# ddrive-esp-deadrail-1-3.net
KiCad netlist of a schematic drawn in EAGLE
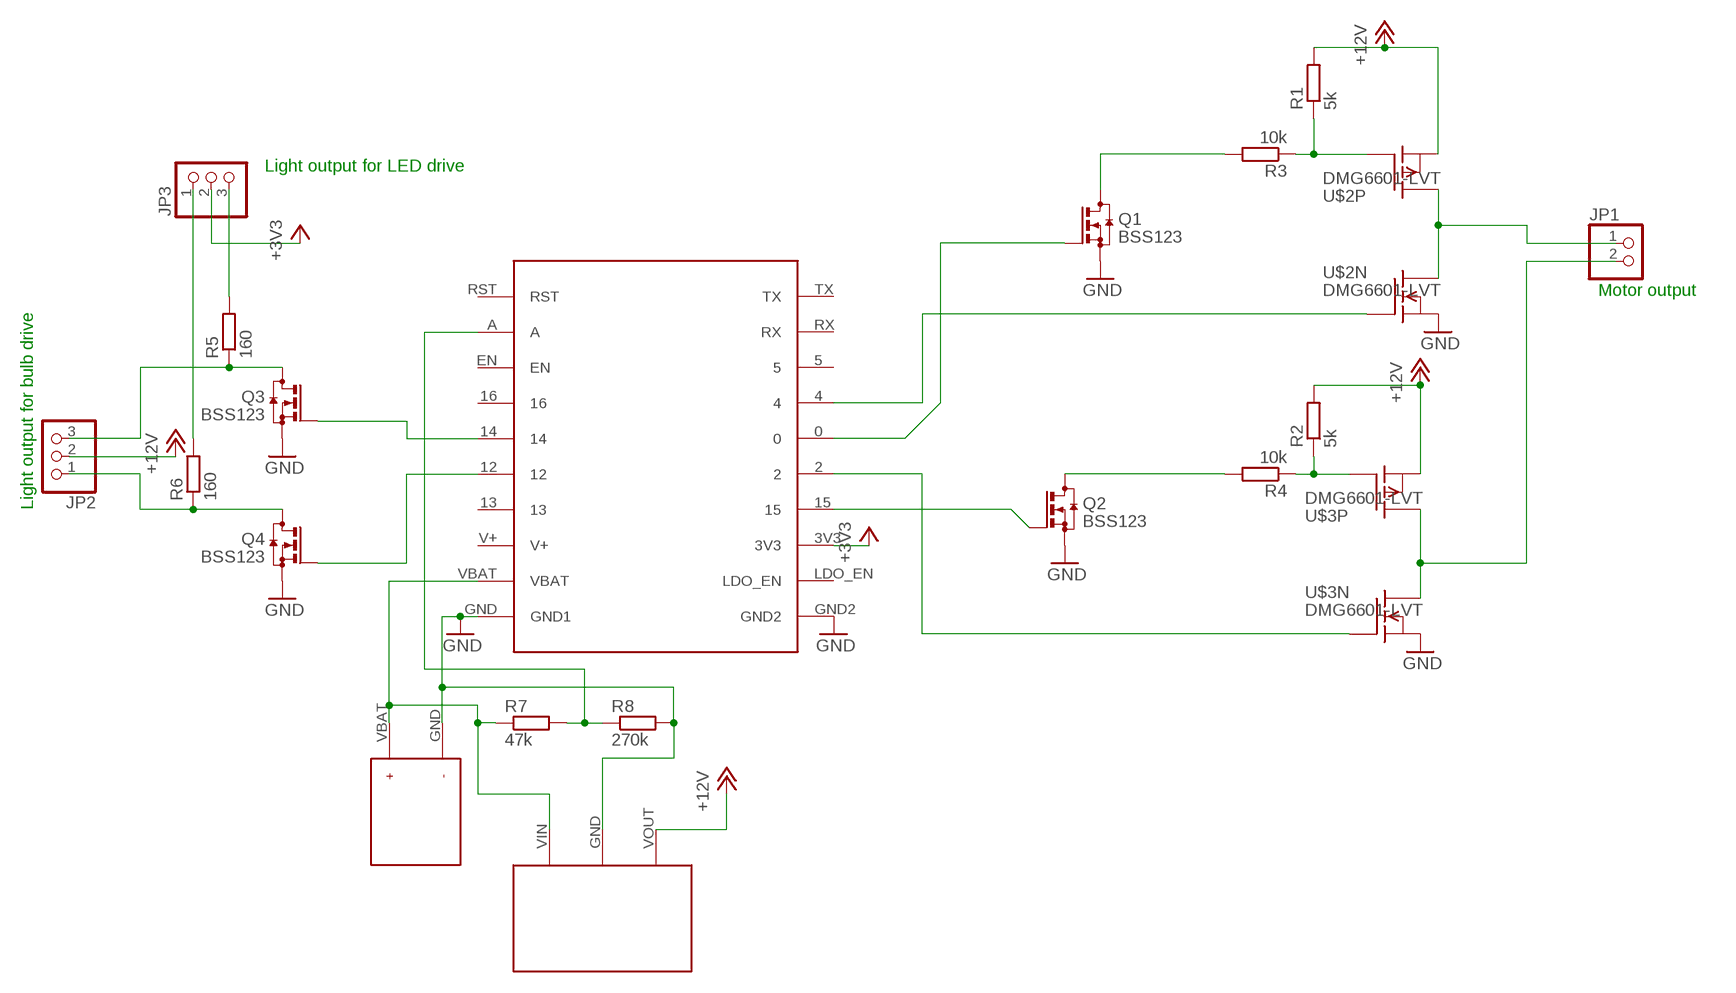
[diagram p0: schematic, sheet 1]

(export (version "E")
  (design (tool "Eeschema 10.0.6"))
  (components
    (comp (ref "JP1")
      (value "PINHD-1X2")
      (footprint "eagle-import:1X02")
      (libsource (lib "eagle-import") (part "PINHD-1X2"))
    )
    (comp (ref "JP2")
      (value "PINHD-1X3")
      (footprint "eagle-import:1X03")
      (libsource (lib "eagle-import") (part "PINHD-1X3"))
    )
    (comp (ref "JP3")
      (value "PINHD-1X3")
      (footprint "eagle-import:1X03")
      (libsource (lib "eagle-import") (part "PINHD-1X3"))
    )
    (comp (ref "Q1")
      (value "BSS123")
      (footprint "eagle-import:SOT23")
      (libsource (lib "eagle-import") (part "BSS123"))
    )
    (comp (ref "Q2")
      (value "BSS123")
      (footprint "eagle-import:SOT23")
      (libsource (lib "eagle-import") (part "BSS123"))
    )
    (comp (ref "Q3")
      (value "BSS123")
      (footprint "eagle-import:SOT23")
      (libsource (lib "eagle-import") (part "BSS123"))
    )
    (comp (ref "Q4")
      (value "BSS123")
      (footprint "eagle-import:SOT23")
      (libsource (lib "eagle-import") (part "BSS123"))
    )
    (comp (ref "R1")
      (value "5k")
      (footprint "eagle-import:R0805")
      (libsource (lib "eagle-import") (part "R-EU_R0805"))
    )
    (comp (ref "R2")
      (value "5k")
      (footprint "eagle-import:R0805")
      (libsource (lib "eagle-import") (part "R-EU_R0805"))
    )
    (comp (ref "R3")
      (value "10k")
      (footprint "eagle-import:R0805")
      (libsource (lib "eagle-import") (part "R-EU_R0805"))
    )
    (comp (ref "R4")
      (value "10k")
      (footprint "eagle-import:R0805")
      (libsource (lib "eagle-import") (part "R-EU_R0805"))
    )
    (comp (ref "R5")
      (value "160")
      (footprint "eagle-import:R0805")
      (libsource (lib "eagle-import") (part "R-EU_R0805"))
    )
    (comp (ref "R6")
      (value "160")
      (footprint "eagle-import:R0805")
      (libsource (lib "eagle-import") (part "R-EU_R0805"))
    )
    (comp (ref "R7")
      (value "47k")
      (footprint "eagle-import:R0805")
      (libsource (lib "eagle-import") (part "R-EU_R0805"))
    )
    (comp (ref "R8")
      (value "270k")
      (footprint "eagle-import:R0805")
      (libsource (lib "eagle-import") (part "R-EU_R0805"))
    )
    (comp (ref "U$1")
      (value "ESP12-HUZZAH")
      (footprint "eagle-import:ESP12-HUZZAH")
      (libsource (lib "eagle-import") (part "ESP12-HUZZAH"))
    )
    (comp (ref "U$2")
      (value "DMG6601-LVT")
      (footprint "eagle-import:TSOT-26")
      (libsource (lib "eagle-import") (part "DMG6601-LVT"))
    )
    (comp (ref "U$3")
      (value "DMG6601-LVT")
      (footprint "eagle-import:TSOT-26")
      (libsource (lib "eagle-import") (part "DMG6601-LVT"))
    )
    (comp (ref "U$4")
      (value "JST-PINHD")
      (footprint "eagle-import:JST-PINHDR")
      (libsource (lib "eagle-import") (part "JST-PINHD"))
    )
    (comp (ref "U$5")
      (value "POLOLU-VREG12")
      (footprint "eagle-import:POLOLU-REGULATOR")
      (libsource (lib "eagle-import") (part "POLOLU-VREG12"))
    )
  )
  (nets
    (net (code "1") (name "+3V3") (class "Default")
      (node (ref "JP3") (pin "2") (pinfunction "2_2") (pintype "passive"))
      (node (ref "U$1") (pin "3V3") (pinfunction "3V3_3V3") (pintype "power_in"))
    )
    (net (code "2") (name "+12V") (class "Default")
      (node (ref "JP2") (pin "2") (pinfunction "2_2") (pintype "passive"))
      (node (ref "R1") (pin "2") (pinfunction "2_2") (pintype "passive"))
      (node (ref "R2") (pin "2") (pinfunction "2_2") (pintype "passive"))
      (node (ref "U$2") (pin "2") (pinfunction "S_2") (pintype "passive"))
      (node (ref "U$3") (pin "2") (pinfunction "S_2") (pintype "passive"))
      (node (ref "U$5") (pin "VOUT") (pinfunction "VOUT_VOUT") (pintype "bidirectional"))
    )
    (net (code "3") (name "/V+") (class "Default")
      (node (ref "U$1") (pin "V+") (pinfunction "V+_V+") (pintype "power_in"))
    )
    (net (code "4") (name "GND") (class "Default")
      (node (ref "Q1") (pin "2") (pinfunction "S_2") (pintype "passive"))
      (node (ref "Q2") (pin "2") (pinfunction "S_2") (pintype "passive"))
      (node (ref "Q3") (pin "2") (pinfunction "S_2") (pintype "passive"))
      (node (ref "Q4") (pin "2") (pinfunction "S_2") (pintype "passive"))
      (node (ref "R8") (pin "2") (pinfunction "2_2") (pintype "passive"))
      (node (ref "U$1") (pin "GND") (pinfunction "GND1_GND") (pintype "power_in"))
      (node (ref "U$1") (pin "GND2") (pinfunction "GND2_GND2") (pintype "power_in"))
      (node (ref "U$2") (pin "5") (pinfunction "S_5") (pintype "passive"))
      (node (ref "U$3") (pin "5") (pinfunction "S_5") (pintype "passive"))
      (node (ref "U$4") (pin "GND") (pinfunction "P$1_GND") (pintype "power_in"))
      (node (ref "U$5") (pin "GND") (pinfunction "GND_GND") (pintype "bidirectional"))
    )
    (net (code "5") (name "Net-(JP3-Pad1)") (class "Default")
      (node (ref "JP3") (pin "1") (pinfunction "1_1") (pintype "passive"))
      (node (ref "R6") (pin "2") (pinfunction "2_2") (pintype "passive"))
    )
    (net (code "6") (name "Net-(JP3-Pad3)") (class "Default")
      (node (ref "JP3") (pin "3") (pinfunction "3_3") (pintype "passive"))
      (node (ref "R5") (pin "2") (pinfunction "2_2") (pintype "passive"))
    )
    (net (code "7") (name "Net-(Q1-D)") (class "Default")
      (node (ref "Q1") (pin "3") (pinfunction "D_3") (pintype "passive"))
      (node (ref "R3") (pin "2") (pinfunction "2_2") (pintype "passive"))
    )
    (net (code "8") (name "Net-(Q1-G)") (class "Default")
      (node (ref "Q1") (pin "1") (pinfunction "G_1") (pintype "passive"))
      (node (ref "U$1") (pin "0") (pinfunction "0_0") (pintype "bidirectional"))
    )
    (net (code "9") (name "Net-(Q2-D)") (class "Default")
      (node (ref "Q2") (pin "3") (pinfunction "D_3") (pintype "passive"))
      (node (ref "R4") (pin "2") (pinfunction "2_2") (pintype "passive"))
    )
    (net (code "10") (name "Net-(Q2-G)") (class "Default")
      (node (ref "Q2") (pin "1") (pinfunction "G_1") (pintype "passive"))
      (node (ref "U$1") (pin "15") (pinfunction "15_15") (pintype "bidirectional"))
    )
    (net (code "11") (name "Net-(Q3-D)") (class "Default")
      (node (ref "JP2") (pin "3") (pinfunction "3_3") (pintype "passive"))
      (node (ref "Q3") (pin "3") (pinfunction "D_3") (pintype "passive"))
      (node (ref "R5") (pin "1") (pinfunction "1_1") (pintype "passive"))
    )
    (net (code "12") (name "Net-(Q3-G)") (class "Default")
      (node (ref "Q3") (pin "1") (pinfunction "G_1") (pintype "passive"))
      (node (ref "U$1") (pin "14") (pinfunction "14_14") (pintype "bidirectional"))
    )
    (net (code "13") (name "Net-(Q4-D)") (class "Default")
      (node (ref "JP2") (pin "1") (pinfunction "1_1") (pintype "passive"))
      (node (ref "Q4") (pin "3") (pinfunction "D_3") (pintype "passive"))
      (node (ref "R6") (pin "1") (pinfunction "1_1") (pintype "passive"))
    )
    (net (code "14") (name "Net-(Q4-G)") (class "Default")
      (node (ref "Q4") (pin "1") (pinfunction "G_1") (pintype "passive"))
      (node (ref "U$1") (pin "12") (pinfunction "12_12") (pintype "bidirectional"))
    )
    (net (code "15") (name "Net-(R7-Pad2)") (class "Default")
      (node (ref "R7") (pin "2") (pinfunction "2_2") (pintype "passive"))
      (node (ref "R8") (pin "1") (pinfunction "1_1") (pintype "passive"))
      (node (ref "U$1") (pin "A") (pinfunction "A_A") (pintype "bidirectional"))
    )
    (net (code "16") (name "Net-(U$2A-D)") (class "Default")
      (node (ref "JP1") (pin "1") (pinfunction "1_1") (pintype "passive"))
      (node (ref "U$2") (pin "4") (pinfunction "D_4") (pintype "passive"))
      (node (ref "U$2") (pin "6") (pinfunction "D_6") (pintype "passive"))
    )
    (net (code "17") (name "Net-(U$2A-G)") (class "Default")
      (node (ref "U$1") (pin "4") (pinfunction "4_4") (pintype "bidirectional"))
      (node (ref "U$2") (pin "1") (pinfunction "G_1") (pintype "passive"))
    )
    (net (code "18") (name "Net-(U$2B-G)") (class "Default")
      (node (ref "R1") (pin "1") (pinfunction "1_1") (pintype "passive"))
      (node (ref "R3") (pin "1") (pinfunction "1_1") (pintype "passive"))
      (node (ref "U$2") (pin "3") (pinfunction "G_3") (pintype "passive"))
    )
    (net (code "19") (name "Net-(U$3A-D)") (class "Default")
      (node (ref "JP1") (pin "2") (pinfunction "2_2") (pintype "passive"))
      (node (ref "U$3") (pin "4") (pinfunction "D_4") (pintype "passive"))
      (node (ref "U$3") (pin "6") (pinfunction "D_6") (pintype "passive"))
    )
    (net (code "20") (name "Net-(U$3A-G)") (class "Default")
      (node (ref "U$1") (pin "2") (pinfunction "2_2") (pintype "bidirectional"))
      (node (ref "U$3") (pin "1") (pinfunction "G_1") (pintype "passive"))
    )
    (net (code "21") (name "Net-(U$3B-G)") (class "Default")
      (node (ref "R2") (pin "1") (pinfunction "1_1") (pintype "passive"))
      (node (ref "R4") (pin "1") (pinfunction "1_1") (pintype "passive"))
      (node (ref "U$3") (pin "3") (pinfunction "G_3") (pintype "passive"))
    )
    (net (code "22") (name "Net-(U$4-P$2)") (class "Default")
      (node (ref "R7") (pin "1") (pinfunction "1_1") (pintype "passive"))
      (node (ref "U$1") (pin "VBAT") (pinfunction "VBAT_VBAT") (pintype "power_in"))
      (node (ref "U$4") (pin "VBAT") (pinfunction "P$2_VBAT") (pintype "power_in"))
      (node (ref "U$5") (pin "VIN") (pinfunction "VIN_VIN") (pintype "bidirectional"))
    )
    (net (code "23") (name "unconnected-(U$1-Pad5)") (class "Default")
      (node (ref "U$1") (pin "5") (pinfunction "5_5") (pintype "bidirectional"))
    )
    (net (code "24") (name "unconnected-(U$1-Pad13)") (class "Default")
      (node (ref "U$1") (pin "13") (pinfunction "13_13") (pintype "bidirectional"))
    )
    (net (code "25") (name "unconnected-(U$1-Pad16)") (class "Default")
      (node (ref "U$1") (pin "16") (pinfunction "16_16") (pintype "bidirectional"))
    )
    (net (code "26") (name "unconnected-(U$1-PadEN)") (class "Default")
      (node (ref "U$1") (pin "EN") (pinfunction "EN_EN") (pintype "bidirectional"))
    )
    (net (code "27") (name "unconnected-(U$1-PadLDO_EN)") (class "Default")
      (node (ref "U$1") (pin "LDO_EN") (pinfunction "LDO_EN_LDO_EN") (pintype "bidirectional"))
    )
    (net (code "28") (name "unconnected-(U$1-PadRST)") (class "Default")
      (node (ref "U$1") (pin "RST") (pinfunction "RST_RST") (pintype "bidirectional"))
    )
    (net (code "29") (name "unconnected-(U$1-PadRX)") (class "Default")
      (node (ref "U$1") (pin "RX") (pinfunction "RX_RX") (pintype "bidirectional"))
    )
    (net (code "30") (name "unconnected-(U$1-PadTX)") (class "Default")
      (node (ref "U$1") (pin "TX") (pinfunction "TX_TX") (pintype "bidirectional"))
    )
  )
)
